# carrier_board.net
KiCad netlist of a schematic drawn in EAGLE
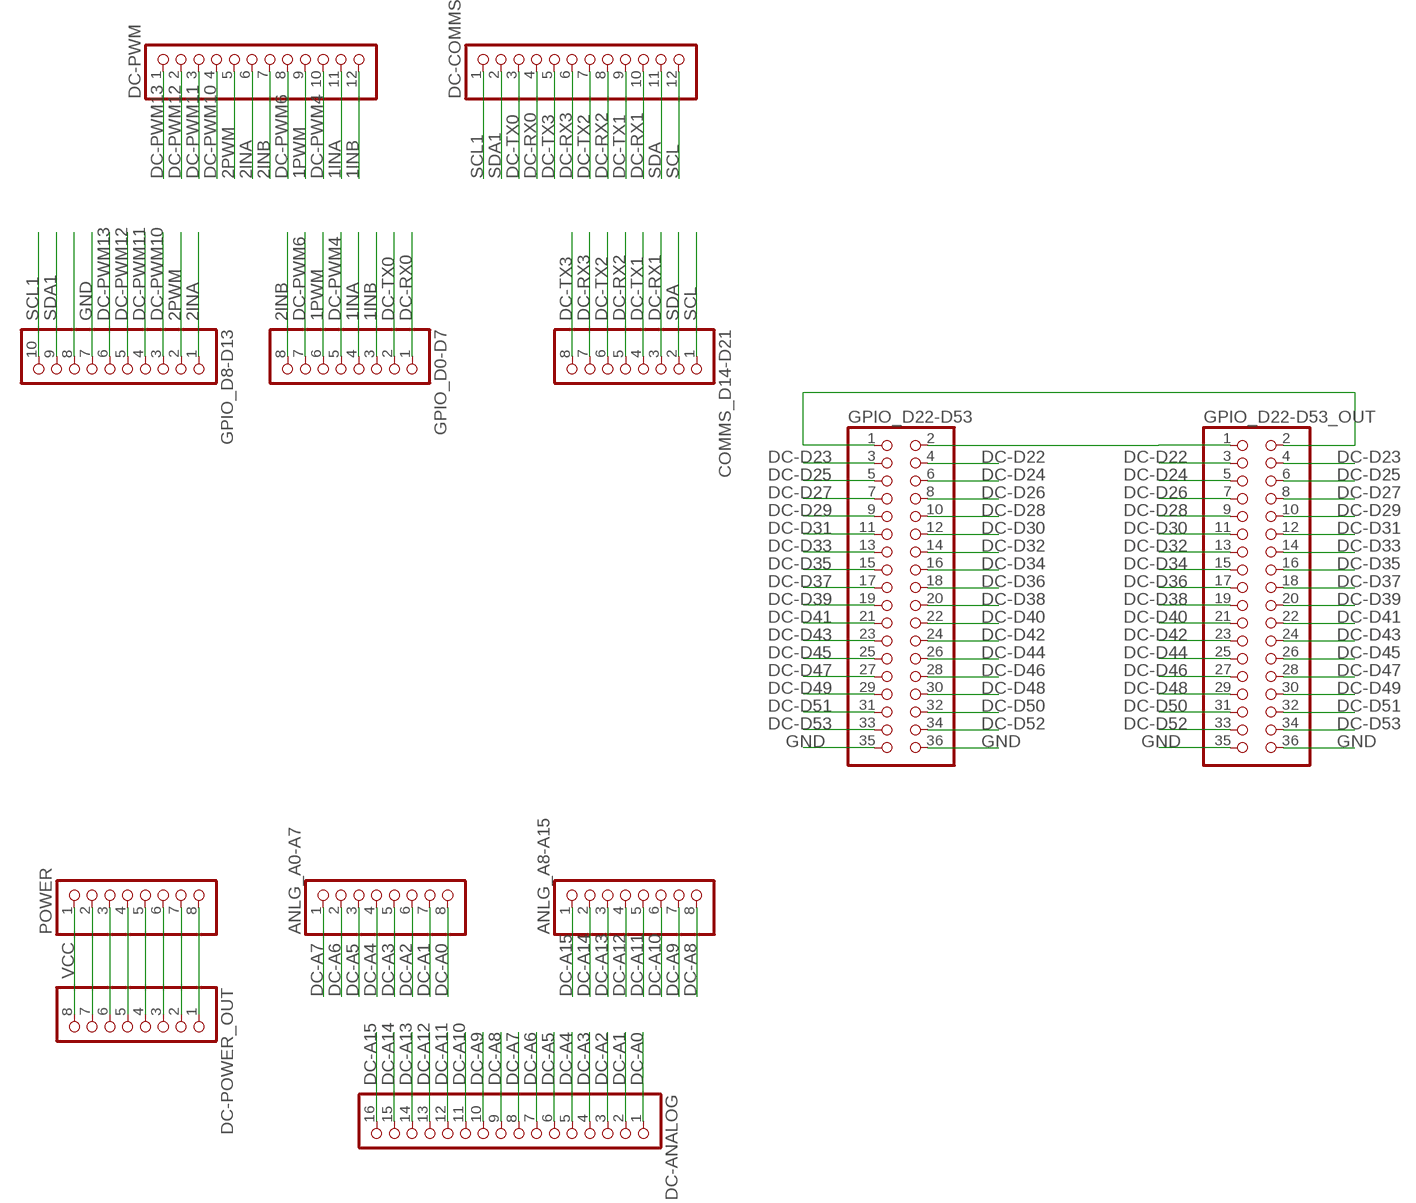
[diagram p0: schematic, sheet 1]
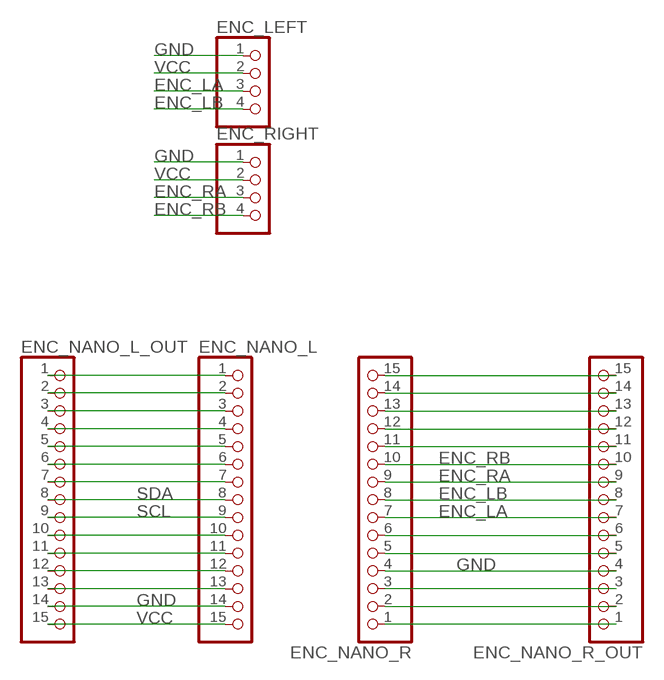
[diagram p1: schematic, sheet 2]
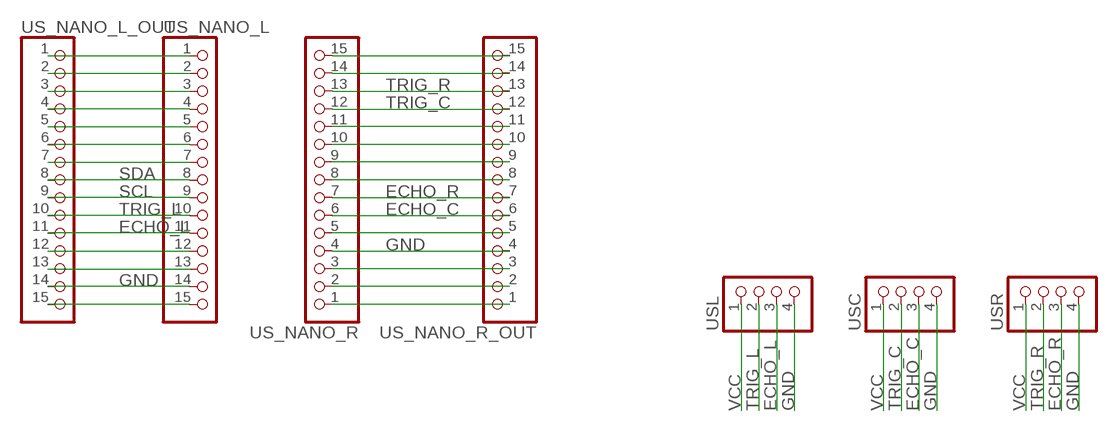
[diagram p2: schematic, sheet 3]
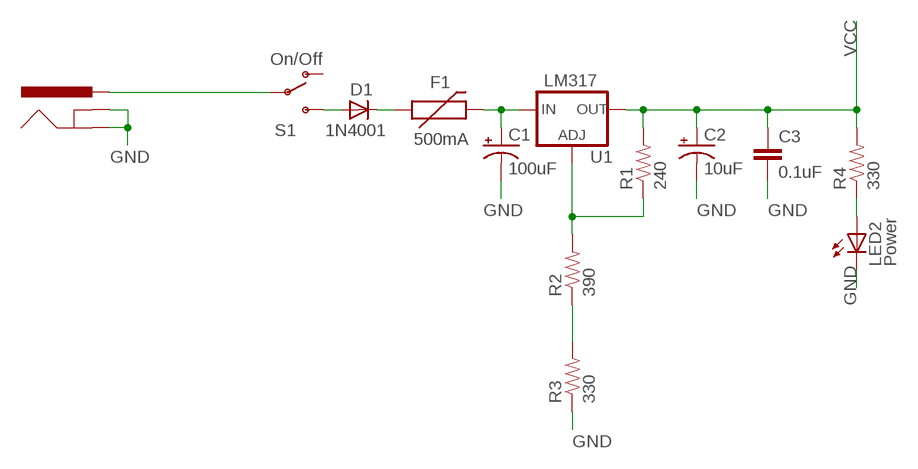
[diagram p3: schematic, sheet 4]
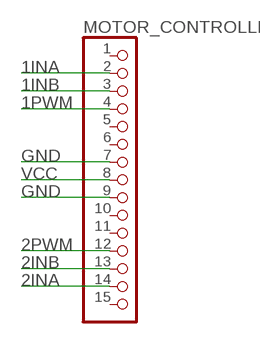
[diagram p4: schematic, sheet 5]

(export (version "E")
  (design (tool "Eeschema 10.0.6"))
  (components
    (comp (ref "ENC_LEFT")
      (value "PINHD-1X4/90")
      (footprint "eagle-import:1X04_90")
      (libsource (lib "eagle-import") (part "PINHD-1X4/90"))
    )
    (comp (ref "ENC_NANO_L")
      (value "PINHD-1X15")
      (footprint "eagle-import:1X15")
      (libsource (lib "eagle-import") (part "PINHD-1X15"))
    )
    (comp (ref "ENC_NANO_L_OUT")
      (value "PINHD-1X15")
      (footprint "eagle-import:1X15")
      (libsource (lib "eagle-import") (part "PINHD-1X15"))
    )
    (comp (ref "ENC_NANO_R")
      (value "PINHD-1X15")
      (footprint "eagle-import:1X15")
      (libsource (lib "eagle-import") (part "PINHD-1X15"))
    )
    (comp (ref "ENC_NANO_R_OUT")
      (value "PINHD-1X15")
      (footprint "eagle-import:1X15")
      (libsource (lib "eagle-import") (part "PINHD-1X15"))
    )
    (comp (ref "ENC_RIGHT")
      (value "PINHD-1X4/90")
      (footprint "eagle-import:1X04_90")
      (libsource (lib "eagle-import") (part "PINHD-1X4/90"))
    )
    (comp (ref "MOTOR_CONTROLLER")
      (value "PINHD-1X15")
      (footprint "eagle-import:1X15")
      (libsource (lib "eagle-import") (part "PINHD-1X15"))
    )
    (comp (ref "ANLG_A0-A7")
      (value "PINHD-1X8")
      (footprint "eagle-import:1X08")
      (libsource (lib "eagle-import") (part "PINHD-1X8"))
    )
    (comp (ref "ANLG_A8-A15")
      (value "PINHD-1X8")
      (footprint "eagle-import:1X08")
      (libsource (lib "eagle-import") (part "PINHD-1X8"))
    )
    (comp (ref "COMMS_D14-D21")
      (value "PINHD-1X8")
      (footprint "eagle-import:1X08")
      (libsource (lib "eagle-import") (part "PINHD-1X8"))
    )
    (comp (ref "DC-ANALOG")
      (value "PINHD-1X16")
      (footprint "eagle-import:1X16")
      (libsource (lib "eagle-import") (part "PINHD-1X16"))
    )
    (comp (ref "DC-COMMS")
      (value "PINHD-1X12")
      (footprint "eagle-import:1X12")
      (libsource (lib "eagle-import") (part "PINHD-1X12"))
    )
    (comp (ref "DC-POWER_OUT")
      (value "PINHD-1X8")
      (footprint "eagle-import:1X08")
      (libsource (lib "eagle-import") (part "PINHD-1X8"))
    )
    (comp (ref "DC-PWM")
      (value "PINHD-1X12")
      (footprint "eagle-import:1X12")
      (libsource (lib "eagle-import") (part "PINHD-1X12"))
    )
    (comp (ref "GPIO_D0-D7")
      (value "PINHD-1X8")
      (footprint "eagle-import:1X08")
      (fields (field (name "SPICEPREFIX") "X"))
      (libsource (lib "eagle-import") (part "PINHD-1X8"))
    )
    (comp (ref "GPIO_D8-D13")
      (value "PINHD-1X10")
      (footprint "eagle-import:1X10")
      (libsource (lib "eagle-import") (part "PINHD-1X10"))
    )
    (comp (ref "GPIO_D22-D53")
      (value "PINHD-2X18")
      (footprint "eagle-import:2X18")
      (libsource (lib "eagle-import") (part "PINHD-2X18"))
    )
    (comp (ref "GPIO_D22-D53_OUT")
      (value "PINHD-2X18")
      (footprint "eagle-import:2X18")
      (libsource (lib "eagle-import") (part "PINHD-2X18"))
    )
    (comp (ref "POWER")
      (value "PINHD-1X8")
      (footprint "eagle-import:1X08")
      (libsource (lib "eagle-import") (part "PINHD-1X8"))
    )
    (comp (ref "USC")
      (value "PINHD-1X4/90")
      (footprint "eagle-import:1X04_90")
      (libsource (lib "eagle-import") (part "PINHD-1X4/90"))
    )
    (comp (ref "USL")
      (value "PINHD-1X4/90")
      (footprint "eagle-import:1X04_90")
      (libsource (lib "eagle-import") (part "PINHD-1X4/90"))
    )
    (comp (ref "USR")
      (value "PINHD-1X4/90")
      (footprint "eagle-import:1X04_90")
      (libsource (lib "eagle-import") (part "PINHD-1X4/90"))
    )
    (comp (ref "US_NANO_L")
      (value "PINHD-1X15")
      (footprint "eagle-import:1X15")
      (libsource (lib "eagle-import") (part "PINHD-1X15"))
    )
    (comp (ref "US_NANO_L_OUT")
      (value "PINHD-1X15")
      (footprint "eagle-import:1X15")
      (libsource (lib "eagle-import") (part "PINHD-1X15"))
    )
    (comp (ref "US_NANO_R")
      (value "PINHD-1X15")
      (footprint "eagle-import:1X15")
      (libsource (lib "eagle-import") (part "PINHD-1X15"))
    )
    (comp (ref "US_NANO_R_OUT")
      (value "PINHD-1X15")
      (footprint "eagle-import:1X15")
      (libsource (lib "eagle-import") (part "PINHD-1X15"))
    )
    (comp (ref "C1")
      (value "100uF")
      (footprint "eagle-import:CPOL-RADIAL-100UF-25V")
      (libsource (lib "eagle-import") (part "CAP_POLPTH1"))
    )
    (comp (ref "C2")
      (value "10uF")
      (footprint "eagle-import:CPOL-RADIAL-10UF-25V")
      (libsource (lib "eagle-import") (part "CAP_POLPTH2"))
    )
    (comp (ref "C3")
      (value "0.1uF")
      (footprint "eagle-import:CAP-PTH-SMALL2")
      (libsource (lib "eagle-import") (part "CAPPTH2"))
    )
    (comp (ref "D1")
      (value "1N4001")
      (footprint "eagle-import:DIODE-0.4")
      (libsource (lib "eagle-import") (part "DIODEPTH"))
    )
    (comp (ref "F1")
      (value "500mA")
      (footprint "eagle-import:PTC")
      (libsource (lib "eagle-import") (part "PTCPTH"))
    )
    (comp (ref "J1")
      (value "POWER_JACKPTH")
      (footprint "eagle-import:POWER_JACK_PTH")
      (libsource (lib "eagle-import") (part "POWER_JACKPTH"))
    )
    (comp (ref "LED2")
      (value "Power")
      (footprint "eagle-import:LED5MM")
      (libsource (lib "eagle-import") (part "LED5MM"))
    )
    (comp (ref "R1")
      (value "240")
      (footprint "eagle-import:AXIAL-0.3")
      (libsource (lib "eagle-import") (part "RESISTORPTH1"))
    )
    (comp (ref "R2")
      (value "390")
      (footprint "eagle-import:AXIAL-0.3")
      (libsource (lib "eagle-import") (part "RESISTORPTH1"))
    )
    (comp (ref "R3")
      (value "330")
      (footprint "eagle-import:AXIAL-0.3")
      (libsource (lib "eagle-import") (part "RESISTORPTH1"))
    )
    (comp (ref "R4")
      (value "330")
      (footprint "eagle-import:AXIAL-0.3")
      (libsource (lib "eagle-import") (part "RESISTORPTH1"))
    )
    (comp (ref "S1")
      (value "On/Off")
      (footprint "eagle-import:SWITCH-SPST")
      (libsource (lib "eagle-import") (part "SWITCH-SPSTPTH"))
    )
    (comp (ref "U1")
      (value "LM317")
      (footprint "eagle-import:TO220-ADJ")
      (libsource (lib "eagle-import") (part "V_REG_317SINK"))
    )
  )
  (nets
    (net (code "1") (name "1INA") (class "Default")
      (node (ref "DC-PWM") (pin "11") (pinfunction "11_11") (pintype "passive"))
      (node (ref "GPIO_D0-D7") (pin "4") (pinfunction "4_4") (pintype "passive"))
      (node (ref "MOTOR_CONTROLLER") (pin "2") (pinfunction "2_2") (pintype "passive"))
    )
    (net (code "2") (name "1INB") (class "Default")
      (node (ref "DC-PWM") (pin "12") (pinfunction "12_12") (pintype "passive"))
      (node (ref "GPIO_D0-D7") (pin "3") (pinfunction "3_3") (pintype "passive"))
      (node (ref "MOTOR_CONTROLLER") (pin "3") (pinfunction "3_3") (pintype "passive"))
    )
    (net (code "3") (name "1PWM") (class "Default")
      (node (ref "DC-PWM") (pin "9") (pinfunction "9_9") (pintype "passive"))
      (node (ref "GPIO_D0-D7") (pin "6") (pinfunction "6_6") (pintype "passive"))
      (node (ref "MOTOR_CONTROLLER") (pin "4") (pinfunction "4_4") (pintype "passive"))
    )
    (net (code "4") (name "2INA") (class "Default")
      (node (ref "DC-PWM") (pin "6") (pinfunction "6_6") (pintype "passive"))
      (node (ref "GPIO_D8-D13") (pin "1") (pinfunction "1_1") (pintype "passive"))
      (node (ref "MOTOR_CONTROLLER") (pin "14") (pinfunction "14_14") (pintype "passive"))
    )
    (net (code "5") (name "2INB") (class "Default")
      (node (ref "DC-PWM") (pin "7") (pinfunction "7_7") (pintype "passive"))
      (node (ref "GPIO_D0-D7") (pin "8") (pinfunction "8_8") (pintype "passive"))
      (node (ref "MOTOR_CONTROLLER") (pin "13") (pinfunction "13_13") (pintype "passive"))
    )
    (net (code "6") (name "2PWM") (class "Default")
      (node (ref "DC-PWM") (pin "5") (pinfunction "5_5") (pintype "passive"))
      (node (ref "GPIO_D8-D13") (pin "2") (pinfunction "2_2") (pintype "passive"))
      (node (ref "MOTOR_CONTROLLER") (pin "12") (pinfunction "12_12") (pintype "passive"))
    )
    (net (code "7") (name "DC-A0") (class "Default")
      (node (ref "ANLG_A0-A7") (pin "8") (pinfunction "8_8") (pintype "passive"))
      (node (ref "DC-ANALOG") (pin "1") (pinfunction "1_1") (pintype "passive"))
    )
    (net (code "8") (name "DC-A1") (class "Default")
      (node (ref "ANLG_A0-A7") (pin "7") (pinfunction "7_7") (pintype "passive"))
      (node (ref "DC-ANALOG") (pin "2") (pinfunction "2_2") (pintype "passive"))
    )
    (net (code "9") (name "DC-A2") (class "Default")
      (node (ref "ANLG_A0-A7") (pin "6") (pinfunction "6_6") (pintype "passive"))
      (node (ref "DC-ANALOG") (pin "3") (pinfunction "3_3") (pintype "passive"))
    )
    (net (code "10") (name "DC-A3") (class "Default")
      (node (ref "ANLG_A0-A7") (pin "5") (pinfunction "5_5") (pintype "passive"))
      (node (ref "DC-ANALOG") (pin "4") (pinfunction "4_4") (pintype "passive"))
    )
    (net (code "11") (name "DC-A4") (class "Default")
      (node (ref "ANLG_A0-A7") (pin "4") (pinfunction "4_4") (pintype "passive"))
      (node (ref "DC-ANALOG") (pin "5") (pinfunction "5_5") (pintype "passive"))
    )
    (net (code "12") (name "DC-A5") (class "Default")
      (node (ref "ANLG_A0-A7") (pin "3") (pinfunction "3_3") (pintype "passive"))
      (node (ref "DC-ANALOG") (pin "6") (pinfunction "6_6") (pintype "passive"))
    )
    (net (code "13") (name "DC-A6") (class "Default")
      (node (ref "ANLG_A0-A7") (pin "2") (pinfunction "2_2") (pintype "passive"))
      (node (ref "DC-ANALOG") (pin "7") (pinfunction "7_7") (pintype "passive"))
    )
    (net (code "14") (name "DC-A7") (class "Default")
      (node (ref "ANLG_A0-A7") (pin "1") (pinfunction "1_1") (pintype "passive"))
      (node (ref "DC-ANALOG") (pin "8") (pinfunction "8_8") (pintype "passive"))
    )
    (net (code "15") (name "DC-A8") (class "Default")
      (node (ref "ANLG_A8-A15") (pin "8") (pinfunction "8_8") (pintype "passive"))
      (node (ref "DC-ANALOG") (pin "9") (pinfunction "9_9") (pintype "passive"))
    )
    (net (code "16") (name "DC-A9") (class "Default")
      (node (ref "ANLG_A8-A15") (pin "7") (pinfunction "7_7") (pintype "passive"))
      (node (ref "DC-ANALOG") (pin "10") (pinfunction "10_10") (pintype "passive"))
    )
    (net (code "17") (name "DC-A10") (class "Default")
      (node (ref "ANLG_A8-A15") (pin "6") (pinfunction "6_6") (pintype "passive"))
      (node (ref "DC-ANALOG") (pin "11") (pinfunction "11_11") (pintype "passive"))
    )
    (net (code "18") (name "DC-A11") (class "Default")
      (node (ref "ANLG_A8-A15") (pin "5") (pinfunction "5_5") (pintype "passive"))
      (node (ref "DC-ANALOG") (pin "12") (pinfunction "12_12") (pintype "passive"))
    )
    (net (code "19") (name "DC-A12") (class "Default")
      (node (ref "ANLG_A8-A15") (pin "4") (pinfunction "4_4") (pintype "passive"))
      (node (ref "DC-ANALOG") (pin "13") (pinfunction "13_13") (pintype "passive"))
    )
    (net (code "20") (name "DC-A13") (class "Default")
      (node (ref "ANLG_A8-A15") (pin "3") (pinfunction "3_3") (pintype "passive"))
      (node (ref "DC-ANALOG") (pin "14") (pinfunction "14_14") (pintype "passive"))
    )
    (net (code "21") (name "DC-A14") (class "Default")
      (node (ref "ANLG_A8-A15") (pin "2") (pinfunction "2_2") (pintype "passive"))
      (node (ref "DC-ANALOG") (pin "15") (pinfunction "15_15") (pintype "passive"))
    )
    (net (code "22") (name "DC-A15") (class "Default")
      (node (ref "ANLG_A8-A15") (pin "1") (pinfunction "1_1") (pintype "passive"))
      (node (ref "DC-ANALOG") (pin "16") (pinfunction "16_16") (pintype "passive"))
    )
    (net (code "23") (name "DC-D22") (class "Default")
      (node (ref "GPIO_D22-D53") (pin "4") (pinfunction "4_4") (pintype "passive"))
      (node (ref "GPIO_D22-D53_OUT") (pin "3") (pinfunction "3_3") (pintype "passive"))
    )
    (net (code "24") (name "DC-D23") (class "Default")
      (node (ref "GPIO_D22-D53") (pin "3") (pinfunction "3_3") (pintype "passive"))
      (node (ref "GPIO_D22-D53_OUT") (pin "4") (pinfunction "4_4") (pintype "passive"))
    )
    (net (code "25") (name "DC-D24") (class "Default")
      (node (ref "GPIO_D22-D53") (pin "6") (pinfunction "6_6") (pintype "passive"))
      (node (ref "GPIO_D22-D53_OUT") (pin "5") (pinfunction "5_5") (pintype "passive"))
    )
    (net (code "26") (name "DC-D25") (class "Default")
      (node (ref "GPIO_D22-D53") (pin "5") (pinfunction "5_5") (pintype "passive"))
      (node (ref "GPIO_D22-D53_OUT") (pin "6") (pinfunction "6_6") (pintype "passive"))
    )
    (net (code "27") (name "DC-D26") (class "Default")
      (node (ref "GPIO_D22-D53") (pin "8") (pinfunction "8_8") (pintype "passive"))
      (node (ref "GPIO_D22-D53_OUT") (pin "7") (pinfunction "7_7") (pintype "passive"))
    )
    (net (code "28") (name "DC-D27") (class "Default")
      (node (ref "GPIO_D22-D53") (pin "7") (pinfunction "7_7") (pintype "passive"))
      (node (ref "GPIO_D22-D53_OUT") (pin "8") (pinfunction "8_8") (pintype "passive"))
    )
    (net (code "29") (name "DC-D28") (class "Default")
      (node (ref "GPIO_D22-D53") (pin "10") (pinfunction "10_10") (pintype "passive"))
      (node (ref "GPIO_D22-D53_OUT") (pin "9") (pinfunction "9_9") (pintype "passive"))
    )
    (net (code "30") (name "DC-D29") (class "Default")
      (node (ref "GPIO_D22-D53") (pin "9") (pinfunction "9_9") (pintype "passive"))
      (node (ref "GPIO_D22-D53_OUT") (pin "10") (pinfunction "10_10") (pintype "passive"))
    )
    (net (code "31") (name "DC-D30") (class "Default")
      (node (ref "GPIO_D22-D53") (pin "12") (pinfunction "12_12") (pintype "passive"))
      (node (ref "GPIO_D22-D53_OUT") (pin "11") (pinfunction "11_11") (pintype "passive"))
    )
    (net (code "32") (name "DC-D31") (class "Default")
      (node (ref "GPIO_D22-D53") (pin "11") (pinfunction "11_11") (pintype "passive"))
      (node (ref "GPIO_D22-D53_OUT") (pin "12") (pinfunction "12_12") (pintype "passive"))
    )
    (net (code "33") (name "DC-D32") (class "Default")
      (node (ref "GPIO_D22-D53") (pin "14") (pinfunction "14_14") (pintype "passive"))
      (node (ref "GPIO_D22-D53_OUT") (pin "13") (pinfunction "13_13") (pintype "passive"))
    )
    (net (code "34") (name "DC-D33") (class "Default")
      (node (ref "GPIO_D22-D53") (pin "13") (pinfunction "13_13") (pintype "passive"))
      (node (ref "GPIO_D22-D53_OUT") (pin "14") (pinfunction "14_14") (pintype "passive"))
    )
    (net (code "35") (name "DC-D34") (class "Default")
      (node (ref "GPIO_D22-D53") (pin "16") (pinfunction "16_16") (pintype "passive"))
      (node (ref "GPIO_D22-D53_OUT") (pin "15") (pinfunction "15_15") (pintype "passive"))
    )
    (net (code "36") (name "DC-D35") (class "Default")
      (node (ref "GPIO_D22-D53") (pin "15") (pinfunction "15_15") (pintype "passive"))
      (node (ref "GPIO_D22-D53_OUT") (pin "16") (pinfunction "16_16") (pintype "passive"))
    )
    (net (code "37") (name "DC-D36") (class "Default")
      (node (ref "GPIO_D22-D53") (pin "18") (pinfunction "18_18") (pintype "passive"))
      (node (ref "GPIO_D22-D53_OUT") (pin "17") (pinfunction "17_17") (pintype "passive"))
    )
    (net (code "38") (name "DC-D37") (class "Default")
      (node (ref "GPIO_D22-D53") (pin "17") (pinfunction "17_17") (pintype "passive"))
      (node (ref "GPIO_D22-D53_OUT") (pin "18") (pinfunction "18_18") (pintype "passive"))
    )
    (net (code "39") (name "DC-D38") (class "Default")
      (node (ref "GPIO_D22-D53") (pin "20") (pinfunction "20_20") (pintype "passive"))
      (node (ref "GPIO_D22-D53_OUT") (pin "19") (pinfunction "19_19") (pintype "passive"))
    )
    (net (code "40") (name "DC-D39") (class "Default")
      (node (ref "GPIO_D22-D53") (pin "19") (pinfunction "19_19") (pintype "passive"))
      (node (ref "GPIO_D22-D53_OUT") (pin "20") (pinfunction "20_20") (pintype "passive"))
    )
    (net (code "41") (name "DC-D40") (class "Default")
      (node (ref "GPIO_D22-D53") (pin "22") (pinfunction "22_22") (pintype "passive"))
      (node (ref "GPIO_D22-D53_OUT") (pin "21") (pinfunction "21_21") (pintype "passive"))
    )
    (net (code "42") (name "DC-D41") (class "Default")
      (node (ref "GPIO_D22-D53") (pin "21") (pinfunction "21_21") (pintype "passive"))
      (node (ref "GPIO_D22-D53_OUT") (pin "22") (pinfunction "22_22") (pintype "passive"))
    )
    (net (code "43") (name "DC-D42") (class "Default")
      (node (ref "GPIO_D22-D53") (pin "24") (pinfunction "24_24") (pintype "passive"))
      (node (ref "GPIO_D22-D53_OUT") (pin "23") (pinfunction "23_23") (pintype "passive"))
    )
    (net (code "44") (name "DC-D43") (class "Default")
      (node (ref "GPIO_D22-D53") (pin "23") (pinfunction "23_23") (pintype "passive"))
      (node (ref "GPIO_D22-D53_OUT") (pin "24") (pinfunction "24_24") (pintype "passive"))
    )
    (net (code "45") (name "DC-D44") (class "Default")
      (node (ref "GPIO_D22-D53") (pin "26") (pinfunction "26_26") (pintype "passive"))
      (node (ref "GPIO_D22-D53_OUT") (pin "25") (pinfunction "25_25") (pintype "passive"))
    )
    (net (code "46") (name "DC-D45") (class "Default")
      (node (ref "GPIO_D22-D53") (pin "25") (pinfunction "25_25") (pintype "passive"))
      (node (ref "GPIO_D22-D53_OUT") (pin "26") (pinfunction "26_26") (pintype "passive"))
    )
    (net (code "47") (name "DC-D46") (class "Default")
      (node (ref "GPIO_D22-D53") (pin "28") (pinfunction "28_28") (pintype "passive"))
      (node (ref "GPIO_D22-D53_OUT") (pin "27") (pinfunction "27_27") (pintype "passive"))
    )
    (net (code "48") (name "DC-D47") (class "Default")
      (node (ref "GPIO_D22-D53") (pin "27") (pinfunction "27_27") (pintype "passive"))
      (node (ref "GPIO_D22-D53_OUT") (pin "28") (pinfunction "28_28") (pintype "passive"))
    )
    (net (code "49") (name "DC-D48") (class "Default")
      (node (ref "GPIO_D22-D53") (pin "30") (pinfunction "30_30") (pintype "passive"))
      (node (ref "GPIO_D22-D53_OUT") (pin "29") (pinfunction "29_29") (pintype "passive"))
    )
    (net (code "50") (name "DC-D49") (class "Default")
      (node (ref "GPIO_D22-D53") (pin "29") (pinfunction "29_29") (pintype "passive"))
      (node (ref "GPIO_D22-D53_OUT") (pin "30") (pinfunction "30_30") (pintype "passive"))
    )
    (net (code "51") (name "DC-D50") (class "Default")
      (node (ref "GPIO_D22-D53") (pin "32") (pinfunction "32_32") (pintype "passive"))
      (node (ref "GPIO_D22-D53_OUT") (pin "31") (pinfunction "31_31") (pintype "passive"))
    )
    (net (code "52") (name "DC-D51") (class "Default")
      (node (ref "GPIO_D22-D53") (pin "31") (pinfunction "31_31") (pintype "passive"))
      (node (ref "GPIO_D22-D53_OUT") (pin "32") (pinfunction "32_32") (pintype "passive"))
    )
    (net (code "53") (name "DC-D52") (class "Default")
      (node (ref "GPIO_D22-D53") (pin "34") (pinfunction "34_34") (pintype "passive"))
      (node (ref "GPIO_D22-D53_OUT") (pin "33") (pinfunction "33_33") (pintype "passive"))
    )
    (net (code "54") (name "DC-D53") (class "Default")
      (node (ref "GPIO_D22-D53") (pin "33") (pinfunction "33_33") (pintype "passive"))
      (node (ref "GPIO_D22-D53_OUT") (pin "34") (pinfunction "34_34") (pintype "passive"))
    )
    (net (code "55") (name "DC-PWM4") (class "Default")
      (node (ref "DC-PWM") (pin "10") (pinfunction "10_10") (pintype "passive"))
      (node (ref "GPIO_D0-D7") (pin "5") (pinfunction "5_5") (pintype "passive"))
    )
    (net (code "56") (name "DC-PWM6") (class "Default")
      (node (ref "DC-PWM") (pin "8") (pinfunction "8_8") (pintype "passive"))
      (node (ref "GPIO_D0-D7") (pin "7") (pinfunction "7_7") (pintype "passive"))
    )
    (net (code "57") (name "DC-PWM10") (class "Default")
      (node (ref "DC-PWM") (pin "4") (pinfunction "4_4") (pintype "passive"))
      (node (ref "GPIO_D8-D13") (pin "3") (pinfunction "3_3") (pintype "passive"))
    )
    (net (code "58") (name "DC-PWM11") (class "Default")
      (node (ref "DC-PWM") (pin "3") (pinfunction "3_3") (pintype "passive"))
      (node (ref "GPIO_D8-D13") (pin "4") (pinfunction "4_4") (pintype "passive"))
    )
    (net (code "59") (name "DC-PWM12") (class "Default")
      (node (ref "DC-PWM") (pin "2") (pinfunction "2_2") (pintype "passive"))
      (node (ref "GPIO_D8-D13") (pin "5") (pinfunction "5_5") (pintype "passive"))
    )
    (net (code "60") (name "DC-PWM13") (class "Default")
      (node (ref "DC-PWM") (pin "1") (pinfunction "1_1") (pintype "passive"))
      (node (ref "GPIO_D8-D13") (pin "6") (pinfunction "6_6") (pintype "passive"))
    )
    (net (code "61") (name "DC-RX0") (class "Default")
      (node (ref "DC-COMMS") (pin "4") (pinfunction "4_4") (pintype "passive"))
      (node (ref "GPIO_D0-D7") (pin "1") (pinfunction "1_1") (pintype "passive"))
    )
    (net (code "62") (name "DC-RX1") (class "Default")
      (node (ref "COMMS_D14-D21") (pin "3") (pinfunction "3_3") (pintype "passive"))
      (node (ref "DC-COMMS") (pin "10") (pinfunction "10_10") (pintype "passive"))
    )
    (net (code "63") (name "DC-RX2") (class "Default")
      (node (ref "COMMS_D14-D21") (pin "5") (pinfunction "5_5") (pintype "passive"))
      (node (ref "DC-COMMS") (pin "8") (pinfunction "8_8") (pintype "passive"))
    )
    (net (code "64") (name "DC-RX3") (class "Default")
      (node (ref "COMMS_D14-D21") (pin "7") (pinfunction "7_7") (pintype "passive"))
      (node (ref "DC-COMMS") (pin "6") (pinfunction "6_6") (pintype "passive"))
    )
    (net (code "65") (name "DC-TX0") (class "Default")
      (node (ref "DC-COMMS") (pin "3") (pinfunction "3_3") (pintype "passive"))
      (node (ref "GPIO_D0-D7") (pin "2") (pinfunction "2_2") (pintype "passive"))
    )
    (net (code "66") (name "DC-TX1") (class "Default")
      (node (ref "COMMS_D14-D21") (pin "4") (pinfunction "4_4") (pintype "passive"))
      (node (ref "DC-COMMS") (pin "9") (pinfunction "9_9") (pintype "passive"))
    )
    (net (code "67") (name "DC-TX2") (class "Default")
      (node (ref "COMMS_D14-D21") (pin "6") (pinfunction "6_6") (pintype "passive"))
      (node (ref "DC-COMMS") (pin "7") (pinfunction "7_7") (pintype "passive"))
    )
    (net (code "68") (name "DC-TX3") (class "Default")
      (node (ref "COMMS_D14-D21") (pin "8") (pinfunction "8_8") (pintype "passive"))
      (node (ref "DC-COMMS") (pin "5") (pinfunction "5_5") (pintype "passive"))
    )
    (net (code "69") (name "ECHO_C") (class "Default")
      (node (ref "USC") (pin "3") (pinfunction "3_3") (pintype "passive"))
      (node (ref "US_NANO_R") (pin "6") (pinfunction "6_6") (pintype "passive"))
      (node (ref "US_NANO_R_OUT") (pin "6") (pinfunction "6_6") (pintype "passive"))
    )
    (net (code "70") (name "ECHO_L") (class "Default")
      (node (ref "USL") (pin "3") (pinfunction "3_3") (pintype "passive"))
      (node (ref "US_NANO_L") (pin "11") (pinfunction "11_11") (pintype "passive"))
      (node (ref "US_NANO_L_OUT") (pin "11") (pinfunction "11_11") (pintype "passive"))
    )
    (net (code "71") (name "ECHO_R") (class "Default")
      (node (ref "USR") (pin "3") (pinfunction "3_3") (pintype "passive"))
      (node (ref "US_NANO_R") (pin "7") (pinfunction "7_7") (pintype "passive"))
      (node (ref "US_NANO_R_OUT") (pin "7") (pinfunction "7_7") (pintype "passive"))
    )
    (net (code "72") (name "ENC_LA") (class "Default")
      (node (ref "ENC_LEFT") (pin "3") (pinfunction "3_3") (pintype "passive"))
      (node (ref "ENC_NANO_R") (pin "7") (pinfunction "7_7") (pintype "passive"))
      (node (ref "ENC_NANO_R_OUT") (pin "7") (pinfunction "7_7") (pintype "passive"))
    )
    (net (code "73") (name "ENC_LB") (class "Default")
      (node (ref "ENC_LEFT") (pin "4") (pinfunction "4_4") (pintype "passive"))
      (node (ref "ENC_NANO_R") (pin "8") (pinfunction "8_8") (pintype "passive"))
      (node (ref "ENC_NANO_R_OUT") (pin "8") (pinfunction "8_8") (pintype "passive"))
    )
    (net (code "74") (name "ENC_RA") (class "Default")
      (node (ref "ENC_NANO_R") (pin "9") (pinfunction "9_9") (pintype "passive"))
      (node (ref "ENC_NANO_R_OUT") (pin "9") (pinfunction "9_9") (pintype "passive"))
      (node (ref "ENC_RIGHT") (pin "3") (pinfunction "3_3") (pintype "passive"))
    )
    (net (code "75") (name "ENC_RB") (class "Default")
      (node (ref "ENC_NANO_R") (pin "10") (pinfunction "10_10") (pintype "passive"))
      (node (ref "ENC_NANO_R_OUT") (pin "10") (pinfunction "10_10") (pintype "passive"))
      (node (ref "ENC_RIGHT") (pin "4") (pinfunction "4_4") (pintype "passive"))
    )
    (net (code "76") (name "GND") (class "Default")
      (node (ref "C1") (pin "2") (pinfunction "-_2") (pintype "passive"))
      (node (ref "C2") (pin "2") (pinfunction "-_2") (pintype "passive"))
      (node (ref "C3") (pin "2") (pinfunction "2_2") (pintype "passive"))
      (node (ref "ENC_LEFT") (pin "1") (pinfunction "1_1") (pintype "passive"))
      (node (ref "ENC_NANO_L") (pin "14") (pinfunction "14_14") (pintype "passive"))
      (node (ref "ENC_NANO_L_OUT") (pin "14") (pinfunction "14_14") (pintype "passive"))
      (node (ref "ENC_NANO_R") (pin "4") (pinfunction "4_4") (pintype "passive"))
      (node (ref "ENC_NANO_R_OUT") (pin "4") (pinfunction "4_4") (pintype "passive"))
      (node (ref "ENC_RIGHT") (pin "1") (pinfunction "1_1") (pintype "passive"))
      (node (ref "GPIO_D22-D53") (pin "35") (pinfunction "35_35") (pintype "passive"))
      (node (ref "GPIO_D22-D53") (pin "36") (pinfunction "36_36") (pintype "passive"))
      (node (ref "GPIO_D22-D53_OUT") (pin "35") (pinfunction "35_35") (pintype "passive"))
      (node (ref "GPIO_D22-D53_OUT") (pin "36") (pinfunction "36_36") (pintype "passive"))
      (node (ref "GPIO_D8-D13") (pin "7") (pinfunction "7_7") (pintype "passive"))
      (node (ref "J1") (pin "GND") (pinfunction "GND_GND") (pintype "bidirectional"))
      (node (ref "J1") (pin "GNDBREAK") (pinfunction "GNDBREAK_GNDBREAK") (pintype "bidirectional"))
      (node (ref "LED2") (pin "K") (pinfunction "C_K") (pintype "passive"))
      (node (ref "MOTOR_CONTROLLER") (pin "7") (pinfunction "7_7") (pintype "passive"))
      (node (ref "MOTOR_CONTROLLER") (pin "9") (pinfunction "9_9") (pintype "passive"))
      (node (ref "R3") (pin "P$1") (pinfunction "1_P$1") (pintype "passive"))
      (node (ref "USC") (pin "4") (pinfunction "4_4") (pintype "passive"))
      (node (ref "USL") (pin "4") (pinfunction "4_4") (pintype "passive"))
      (node (ref "USR") (pin "4") (pinfunction "4_4") (pintype "passive"))
      (node (ref "US_NANO_L") (pin "14") (pinfunction "14_14") (pintype "passive"))
      (node (ref "US_NANO_L_OUT") (pin "14") (pinfunction "14_14") (pintype "passive"))
      (node (ref "US_NANO_R") (pin "4") (pinfunction "4_4") (pintype "passive"))
      (node (ref "US_NANO_R_OUT") (pin "4") (pinfunction "4_4") (pintype "passive"))
    )
    (net (code "77") (name "Net-(C1-+)") (class "Default")
      (node (ref "C1") (pin "1") (pinfunction "+_1") (pintype "passive"))
      (node (ref "F1") (pin "P$2") (pinfunction "2_P$2") (pintype "bidirectional"))
      (node (ref "U1") (pin "IN") (pinfunction "IN_IN") (pintype "input"))
    )
    (net (code "78") (name "Net-(DC-POWER_OUT-Pad1)") (class "Default")
      (node (ref "DC-POWER_OUT") (pin "1") (pinfunction "1_1") (pintype "passive"))
      (node (ref "POWER") (pin "8") (pinfunction "8_8") (pintype "passive"))
    )
    (net (code "79") (name "Net-(DC-POWER_OUT-Pad2)") (class "Default")
      (node (ref "DC-POWER_OUT") (pin "2") (pinfunction "2_2") (pintype "passive"))
      (node (ref "POWER") (pin "7") (pinfunction "7_7") (pintype "passive"))
    )
    (net (code "80") (name "Net-(DC-POWER_OUT-Pad3)") (class "Default")
      (node (ref "DC-POWER_OUT") (pin "3") (pinfunction "3_3") (pintype "passive"))
      (node (ref "POWER") (pin "6") (pinfunction "6_6") (pintype "passive"))
    )
    (net (code "81") (name "Net-(DC-POWER_OUT-Pad4)") (class "Default")
      (node (ref "DC-POWER_OUT") (pin "4") (pinfunction "4_4") (pintype "passive"))
      (node (ref "POWER") (pin "5") (pinfunction "5_5") (pintype "passive"))
    )
    (net (code "82") (name "Net-(DC-POWER_OUT-Pad5)") (class "Default")
      (node (ref "DC-POWER_OUT") (pin "5") (pinfunction "5_5") (pintype "passive"))
      (node (ref "POWER") (pin "4") (pinfunction "4_4") (pintype "passive"))
    )
    (net (code "83") (name "Net-(DC-POWER_OUT-Pad6)") (class "Default")
      (node (ref "DC-POWER_OUT") (pin "6") (pinfunction "6_6") (pintype "passive"))
      (node (ref "POWER") (pin "3") (pinfunction "3_3") (pintype "passive"))
    )
    (net (code "84") (name "Net-(DC-POWER_OUT-Pad7)") (class "Default")
      (node (ref "DC-POWER_OUT") (pin "7") (pinfunction "7_7") (pintype "passive"))
      (node (ref "POWER") (pin "2") (pinfunction "2_2") (pintype "passive"))
    )
    (net (code "85") (name "Net-(ENC_NANO_L-Pad1)") (class "Default")
      (node (ref "ENC_NANO_L") (pin "1") (pinfunction "1_1") (pintype "passive"))
      (node (ref "ENC_NANO_L_OUT") (pin "1") (pinfunction "1_1") (pintype "passive"))
    )
    (net (code "86") (name "Net-(ENC_NANO_L-Pad2)") (class "Default")
      (node (ref "ENC_NANO_L") (pin "2") (pinfunction "2_2") (pintype "passive"))
      (node (ref "ENC_NANO_L_OUT") (pin "2") (pinfunction "2_2") (pintype "passive"))
    )
    (net (code "87") (name "Net-(ENC_NANO_L-Pad3)") (class "Default")
      (node (ref "ENC_NANO_L") (pin "3") (pinfunction "3_3") (pintype "passive"))
      (node (ref "ENC_NANO_L_OUT") (pin "3") (pinfunction "3_3") (pintype "passive"))
    )
    (net (code "88") (name "Net-(ENC_NANO_L-Pad4)") (class "Default")
      (node (ref "ENC_NANO_L") (pin "4") (pinfunction "4_4") (pintype "passive"))
      (node (ref "ENC_NANO_L_OUT") (pin "4") (pinfunction "4_4") (pintype "passive"))
    )
    (net (code "89") (name "Net-(ENC_NANO_L-Pad5)") (class "Default")
      (node (ref "ENC_NANO_L") (pin "5") (pinfunction "5_5") (pintype "passive"))
      (node (ref "ENC_NANO_L_OUT") (pin "5") (pinfunction "5_5") (pintype "passive"))
    )
    (net (code "90") (name "Net-(ENC_NANO_L-Pad6)") (class "Default")
      (node (ref "ENC_NANO_L") (pin "6") (pinfunction "6_6") (pintype "passive"))
      (node (ref "ENC_NANO_L_OUT") (pin "6") (pinfunction "6_6") (pintype "passive"))
    )
    (net (code "91") (name "Net-(ENC_NANO_L-Pad7)") (class "Default")
      (node (ref "ENC_NANO_L") (pin "7") (pinfunction "7_7") (pintype "passive"))
      (node (ref "ENC_NANO_L_OUT") (pin "7") (pinfunction "7_7") (pintype "passive"))
    )
    (net (code "92") (name "Net-(ENC_NANO_L-Pad10)") (class "Default")
      (node (ref "ENC_NANO_L") (pin "10") (pinfunction "10_10") (pintype "passive"))
      (node (ref "ENC_NANO_L_OUT") (pin "10") (pinfunction "10_10") (pintype "passive"))
    )
    (net (code "93") (name "Net-(ENC_NANO_L-Pad11)") (class "Default")
      (node (ref "ENC_NANO_L") (pin "11") (pinfunction "11_11") (pintype "passive"))
      (node (ref "ENC_NANO_L_OUT") (pin "11") (pinfunction "11_11") (pintype "passive"))
    )
    (net (code "94") (name "Net-(ENC_NANO_L-Pad12)") (class "Default")
      (node (ref "ENC_NANO_L") (pin "12") (pinfunction "12_12") (pintype "passive"))
      (node (ref "ENC_NANO_L_OUT") (pin "12") (pinfunction "12_12") (pintype "passive"))
    )
    (net (code "95") (name "Net-(ENC_NANO_L-Pad13)") (class "Default")
      (node (ref "ENC_NANO_L") (pin "13") (pinfunction "13_13") (pintype "passive"))
      (node (ref "ENC_NANO_L_OUT") (pin "13") (pinfunction "13_13") (pintype "passive"))
    )
    (net (code "96") (name "Net-(ENC_NANO_R-Pad1)") (class "Default")
      (node (ref "ENC_NANO_R") (pin "1") (pinfunction "1_1") (pintype "passive"))
      (node (ref "ENC_NANO_R_OUT") (pin "1") (pinfunction "1_1") (pintype "passive"))
    )
    (net (code "97") (name "Net-(ENC_NANO_R-Pad2)") (class "Default")
      (node (ref "ENC_NANO_R") (pin "2") (pinfunction "2_2") (pintype "passive"))
      (node (ref "ENC_NANO_R_OUT") (pin "2") (pinfunction "2_2") (pintype "passive"))
    )
    (net (code "98") (name "Net-(ENC_NANO_R-Pad3)") (class "Default")
      (node (ref "ENC_NANO_R") (pin "3") (pinfunction "3_3") (pintype "passive"))
      (node (ref "ENC_NANO_R_OUT") (pin "3") (pinfunction "3_3") (pintype "passive"))
    )
    (net (code "99") (name "Net-(ENC_NANO_R-Pad5)") (class "Default")
      (node (ref "ENC_NANO_R") (pin "5") (pinfunction "5_5") (pintype "passive"))
      (node (ref "ENC_NANO_R_OUT") (pin "5") (pinfunction "5_5") (pintype "passive"))
    )
    (net (code "100") (name "Net-(ENC_NANO_R-Pad6)") (class "Default")
      (node (ref "ENC_NANO_R") (pin "6") (pinfunction "6_6") (pintype "passive"))
      (node (ref "ENC_NANO_R_OUT") (pin "6") (pinfunction "6_6") (pintype "passive"))
    )
    (net (code "101") (name "Net-(ENC_NANO_R-Pad11)") (class "Default")
      (node (ref "ENC_NANO_R") (pin "11") (pinfunction "11_11") (pintype "passive"))
      (node (ref "ENC_NANO_R_OUT") (pin "11") (pinfunction "11_11") (pintype "passive"))
    )
    (net (code "102") (name "Net-(ENC_NANO_R-Pad12)") (class "Default")
      (node (ref "ENC_NANO_R") (pin "12") (pinfunction "12_12") (pintype "passive"))
      (node (ref "ENC_NANO_R_OUT") (pin "12") (pinfunction "12_12") (pintype "passive"))
    )
    (net (code "103") (name "Net-(ENC_NANO_R-Pad13)") (class "Default")
      (node (ref "ENC_NANO_R") (pin "13") (pinfunction "13_13") (pintype "passive"))
      (node (ref "ENC_NANO_R_OUT") (pin "13") (pinfunction "13_13") (pintype "passive"))
    )
    (net (code "104") (name "Net-(ENC_NANO_R-Pad14)") (class "Default")
      (node (ref "ENC_NANO_R") (pin "14") (pinfunction "14_14") (pintype "passive"))
      (node (ref "ENC_NANO_R_OUT") (pin "14") (pinfunction "14_14") (pintype "passive"))
    )
    (net (code "105") (name "Net-(ENC_NANO_R-Pad15)") (class "Default")
      (node (ref "ENC_NANO_R") (pin "15") (pinfunction "15_15") (pintype "passive"))
      (node (ref "ENC_NANO_R_OUT") (pin "15") (pinfunction "15_15") (pintype "passive"))
    )
    (net (code "106") (name "Net-(F1-1)") (class "Default")
      (node (ref "D1") (pin "C") (pinfunction "C_C") (pintype "passive"))
      (node (ref "F1") (pin "P$1") (pinfunction "1_P$1") (pintype "bidirectional"))
    )
    (net (code "107") (name "Net-(GPIO_D22-D53-Pad1)") (class "Default")
      (node (ref "GPIO_D22-D53") (pin "1") (pinfunction "1_1") (pintype "passive"))
      (node (ref "GPIO_D22-D53_OUT") (pin "2") (pinfunction "2_2") (pintype "passive"))
    )
    (net (code "108") (name "Net-(GPIO_D22-D53-Pad2)") (class "Default")
      (node (ref "GPIO_D22-D53") (pin "2") (pinfunction "2_2") (pintype "passive"))
      (node (ref "GPIO_D22-D53_OUT") (pin "1") (pinfunction "1_1") (pintype "passive"))
    )
    (net (code "109") (name "Net-(R1-1)") (class "Default")
      (node (ref "R1") (pin "P$1") (pinfunction "1_P$1") (pintype "passive"))
      (node (ref "R2") (pin "P$2") (pinfunction "2_P$2") (pintype "passive"))
      (node (ref "U1") (pin "ADJ") (pinfunction "ADJ_ADJ") (pintype "input"))
    )
    (net (code "110") (name "Net-(R2-1)") (class "Default")
      (node (ref "R2") (pin "P$1") (pinfunction "1_P$1") (pintype "passive"))
      (node (ref "R3") (pin "P$2") (pinfunction "2_P$2") (pintype "passive"))
    )
    (net (code "111") (name "Net-(R4-1)") (class "Default")
      (node (ref "LED2") (pin "A") (pinfunction "A_A") (pintype "passive"))
      (node (ref "R4") (pin "P$1") (pinfunction "1_P$1") (pintype "passive"))
    )
    (net (code "112") (name "Net-(S1-P)") (class "Default")
      (node (ref "J1") (pin "PWR") (pinfunction "PWR_PWR") (pintype "bidirectional"))
      (node (ref "S1") (pin "2") (pinfunction "P_2") (pintype "passive"))
    )
    (net (code "113") (name "Net-(S1-S)") (class "Default")
      (node (ref "D1") (pin "A") (pinfunction "A_A") (pintype "passive"))
      (node (ref "S1") (pin "3") (pinfunction "S_3") (pintype "passive"))
    )
    (net (code "114") (name "Net-(US_NANO_L-Pad1)") (class "Default")
      (node (ref "US_NANO_L") (pin "1") (pinfunction "1_1") (pintype "passive"))
      (node (ref "US_NANO_L_OUT") (pin "1") (pinfunction "1_1") (pintype "passive"))
    )
    (net (code "115") (name "Net-(US_NANO_L-Pad2)") (class "Default")
      (node (ref "US_NANO_L") (pin "2") (pinfunction "2_2") (pintype "passive"))
      (node (ref "US_NANO_L_OUT") (pin "2") (pinfunction "2_2") (pintype "passive"))
    )
    (net (code "116") (name "Net-(US_NANO_L-Pad3)") (class "Default")
      (node (ref "US_NANO_L") (pin "3") (pinfunction "3_3") (pintype "passive"))
      (node (ref "US_NANO_L_OUT") (pin "3") (pinfunction "3_3") (pintype "passive"))
    )
    (net (code "117") (name "Net-(US_NANO_L-Pad4)") (class "Default")
      (node (ref "US_NANO_L") (pin "4") (pinfunction "4_4") (pintype "passive"))
      (node (ref "US_NANO_L_OUT") (pin "4") (pinfunction "4_4") (pintype "passive"))
    )
    (net (code "118") (name "Net-(US_NANO_L-Pad5)") (class "Default")
      (node (ref "US_NANO_L") (pin "5") (pinfunction "5_5") (pintype "passive"))
      (node (ref "US_NANO_L_OUT") (pin "5") (pinfunction "5_5") (pintype "passive"))
    )
    (net (code "119") (name "Net-(US_NANO_L-Pad6)") (class "Default")
      (node (ref "US_NANO_L") (pin "6") (pinfunction "6_6") (pintype "passive"))
      (node (ref "US_NANO_L_OUT") (pin "6") (pinfunction "6_6") (pintype "passive"))
    )
    (net (code "120") (name "Net-(US_NANO_L-Pad7)") (class "Default")
      (node (ref "US_NANO_L") (pin "7") (pinfunction "7_7") (pintype "passive"))
      (node (ref "US_NANO_L_OUT") (pin "7") (pinfunction "7_7") (pintype "passive"))
    )
    (net (code "121") (name "Net-(US_NANO_L-Pad12)") (class "Default")
      (node (ref "US_NANO_L") (pin "12") (pinfunction "12_12") (pintype "passive"))
      (node (ref "US_NANO_L_OUT") (pin "12") (pinfunction "12_12") (pintype "passive"))
    )
    (net (code "122") (name "Net-(US_NANO_L-Pad13)") (class "Default")
      (node (ref "US_NANO_L") (pin "13") (pinfunction "13_13") (pintype "passive"))
      (node (ref "US_NANO_L_OUT") (pin "13") (pinfunction "13_13") (pintype "passive"))
    )
    (net (code "123") (name "Net-(US_NANO_L-Pad15)") (class "Default")
      (node (ref "US_NANO_L") (pin "15") (pinfunction "15_15") (pintype "passive"))
      (node (ref "US_NANO_L_OUT") (pin "15") (pinfunction "15_15") (pintype "passive"))
    )
    (net (code "124") (name "Net-(US_NANO_R-Pad1)") (class "Default")
      (node (ref "US_NANO_R") (pin "1") (pinfunction "1_1") (pintype "passive"))
      (node (ref "US_NANO_R_OUT") (pin "1") (pinfunction "1_1") (pintype "passive"))
    )
    (net (code "125") (name "Net-(US_NANO_R-Pad2)") (class "Default")
      (node (ref "US_NANO_R") (pin "2") (pinfunction "2_2") (pintype "passive"))
      (node (ref "US_NANO_R_OUT") (pin "2") (pinfunction "2_2") (pintype "passive"))
    )
    (net (code "126") (name "Net-(US_NANO_R-Pad3)") (class "Default")
      (node (ref "US_NANO_R") (pin "3") (pinfunction "3_3") (pintype "passive"))
      (node (ref "US_NANO_R_OUT") (pin "3") (pinfunction "3_3") (pintype "passive"))
    )
    (net (code "127") (name "Net-(US_NANO_R-Pad5)") (class "Default")
      (node (ref "US_NANO_R") (pin "5") (pinfunction "5_5") (pintype "passive"))
      (node (ref "US_NANO_R_OUT") (pin "5") (pinfunction "5_5") (pintype "passive"))
    )
    (net (code "128") (name "Net-(US_NANO_R-Pad8)") (class "Default")
      (node (ref "US_NANO_R") (pin "8") (pinfunction "8_8") (pintype "passive"))
      (node (ref "US_NANO_R_OUT") (pin "8") (pinfunction "8_8") (pintype "passive"))
    )
    (net (code "129") (name "Net-(US_NANO_R-Pad9)") (class "Default")
      (node (ref "US_NANO_R") (pin "9") (pinfunction "9_9") (pintype "passive"))
      (node (ref "US_NANO_R_OUT") (pin "9") (pinfunction "9_9") (pintype "passive"))
    )
    (net (code "130") (name "Net-(US_NANO_R-Pad10)") (class "Default")
      (node (ref "US_NANO_R") (pin "10") (pinfunction "10_10") (pintype "passive"))
      (node (ref "US_NANO_R_OUT") (pin "10") (pinfunction "10_10") (pintype "passive"))
    )
    (net (code "131") (name "Net-(US_NANO_R-Pad11)") (class "Default")
      (node (ref "US_NANO_R") (pin "11") (pinfunction "11_11") (pintype "passive"))
      (node (ref "US_NANO_R_OUT") (pin "11") (pinfunction "11_11") (pintype "passive"))
    )
    (net (code "132") (name "Net-(US_NANO_R-Pad14)") (class "Default")
      (node (ref "US_NANO_R") (pin "14") (pinfunction "14_14") (pintype "passive"))
      (node (ref "US_NANO_R_OUT") (pin "14") (pinfunction "14_14") (pintype "passive"))
    )
    (net (code "133") (name "Net-(US_NANO_R-Pad15)") (class "Default")
      (node (ref "US_NANO_R") (pin "15") (pinfunction "15_15") (pintype "passive"))
      (node (ref "US_NANO_R_OUT") (pin "15") (pinfunction "15_15") (pintype "passive"))
    )
    (net (code "134") (name "SCL") (class "Default")
      (node (ref "COMMS_D14-D21") (pin "1") (pinfunction "1_1") (pintype "passive"))
      (node (ref "DC-COMMS") (pin "12") (pinfunction "12_12") (pintype "passive"))
      (node (ref "ENC_NANO_L") (pin "9") (pinfunction "9_9") (pintype "passive"))
      (node (ref "ENC_NANO_L_OUT") (pin "9") (pinfunction "9_9") (pintype "passive"))
      (node (ref "US_NANO_L") (pin "9") (pinfunction "9_9") (pintype "passive"))
      (node (ref "US_NANO_L_OUT") (pin "9") (pinfunction "9_9") (pintype "passive"))
    )
    (net (code "135") (name "SCL1") (class "Default")
      (node (ref "DC-COMMS") (pin "1") (pinfunction "1_1") (pintype "passive"))
      (node (ref "GPIO_D8-D13") (pin "10") (pinfunction "10_10") (pintype "passive"))
    )
    (net (code "136") (name "SDA") (class "Default")
      (node (ref "COMMS_D14-D21") (pin "2") (pinfunction "2_2") (pintype "passive"))
      (node (ref "DC-COMMS") (pin "11") (pinfunction "11_11") (pintype "passive"))
      (node (ref "ENC_NANO_L") (pin "8") (pinfunction "8_8") (pintype "passive"))
      (node (ref "ENC_NANO_L_OUT") (pin "8") (pinfunction "8_8") (pintype "passive"))
      (node (ref "US_NANO_L") (pin "8") (pinfunction "8_8") (pintype "passive"))
      (node (ref "US_NANO_L_OUT") (pin "8") (pinfunction "8_8") (pintype "passive"))
    )
    (net (code "137") (name "SDA1") (class "Default")
      (node (ref "DC-COMMS") (pin "2") (pinfunction "2_2") (pintype "passive"))
      (node (ref "GPIO_D8-D13") (pin "9") (pinfunction "9_9") (pintype "passive"))
    )
    (net (code "138") (name "TRIG_C") (class "Default")
      (node (ref "USC") (pin "2") (pinfunction "2_2") (pintype "passive"))
      (node (ref "US_NANO_R") (pin "12") (pinfunction "12_12") (pintype "passive"))
      (node (ref "US_NANO_R_OUT") (pin "12") (pinfunction "12_12") (pintype "passive"))
    )
    (net (code "139") (name "TRIG_L") (class "Default")
      (node (ref "USL") (pin "2") (pinfunction "2_2") (pintype "passive"))
      (node (ref "US_NANO_L") (pin "10") (pinfunction "10_10") (pintype "passive"))
      (node (ref "US_NANO_L_OUT") (pin "10") (pinfunction "10_10") (pintype "passive"))
    )
    (net (code "140") (name "TRIG_R") (class "Default")
      (node (ref "USR") (pin "2") (pinfunction "2_2") (pintype "passive"))
      (node (ref "US_NANO_R") (pin "13") (pinfunction "13_13") (pintype "passive"))
      (node (ref "US_NANO_R_OUT") (pin "13") (pinfunction "13_13") (pintype "passive"))
    )
    (net (code "141") (name "VCC") (class "Default")
      (node (ref "C2") (pin "1") (pinfunction "+_1") (pintype "passive"))
      (node (ref "C3") (pin "1") (pinfunction "1_1") (pintype "passive"))
      (node (ref "DC-POWER_OUT") (pin "8") (pinfunction "8_8") (pintype "passive"))
      (node (ref "ENC_LEFT") (pin "2") (pinfunction "2_2") (pintype "passive"))
      (node (ref "ENC_NANO_L") (pin "15") (pinfunction "15_15") (pintype "passive"))
      (node (ref "ENC_NANO_L_OUT") (pin "15") (pinfunction "15_15") (pintype "passive"))
      (node (ref "ENC_RIGHT") (pin "2") (pinfunction "2_2") (pintype "passive"))
      (node (ref "MOTOR_CONTROLLER") (pin "8") (pinfunction "8_8") (pintype "passive"))
      (node (ref "POWER") (pin "1") (pinfunction "1_1") (pintype "passive"))
      (node (ref "R1") (pin "P$2") (pinfunction "2_P$2") (pintype "passive"))
      (node (ref "R4") (pin "P$2") (pinfunction "2_P$2") (pintype "passive"))
      (node (ref "U1") (pin "OUT") (pinfunction "OUT_OUT") (pintype "output"))
      (node (ref "USC") (pin "1") (pinfunction "1_1") (pintype "passive"))
      (node (ref "USL") (pin "1") (pinfunction "1_1") (pintype "passive"))
      (node (ref "USR") (pin "1") (pinfunction "1_1") (pintype "passive"))
    )
    (net (code "142") (name "unconnected-(GPIO_D8-D13-Pad8)") (class "Default")
      (node (ref "GPIO_D8-D13") (pin "8") (pinfunction "8_8") (pintype "passive"))
    )
    (net (code "143") (name "unconnected-(MOTOR_CONTROLLER-Pad1)") (class "Default")
      (node (ref "MOTOR_CONTROLLER") (pin "1") (pinfunction "1_1") (pintype "passive"))
    )
    (net (code "144") (name "unconnected-(MOTOR_CONTROLLER-Pad5)") (class "Default")
      (node (ref "MOTOR_CONTROLLER") (pin "5") (pinfunction "5_5") (pintype "passive"))
    )
    (net (code "145") (name "unconnected-(MOTOR_CONTROLLER-Pad6)") (class "Default")
      (node (ref "MOTOR_CONTROLLER") (pin "6") (pinfunction "6_6") (pintype "passive"))
    )
    (net (code "146") (name "unconnected-(MOTOR_CONTROLLER-Pad10)") (class "Default")
      (node (ref "MOTOR_CONTROLLER") (pin "10") (pinfunction "10_10") (pintype "passive"))
    )
    (net (code "147") (name "unconnected-(MOTOR_CONTROLLER-Pad11)") (class "Default")
      (node (ref "MOTOR_CONTROLLER") (pin "11") (pinfunction "11_11") (pintype "passive"))
    )
    (net (code "148") (name "unconnected-(MOTOR_CONTROLLER-Pad15)") (class "Default")
      (node (ref "MOTOR_CONTROLLER") (pin "15") (pinfunction "15_15") (pintype "passive"))
    )
    (net (code "149") (name "unconnected-(S1-O-Pad1)") (class "Default")
      (node (ref "S1") (pin "1") (pinfunction "O_1") (pintype "passive"))
    )
  )
)
